# schematics.net
KiCad netlist of a schematic drawn in EAGLE
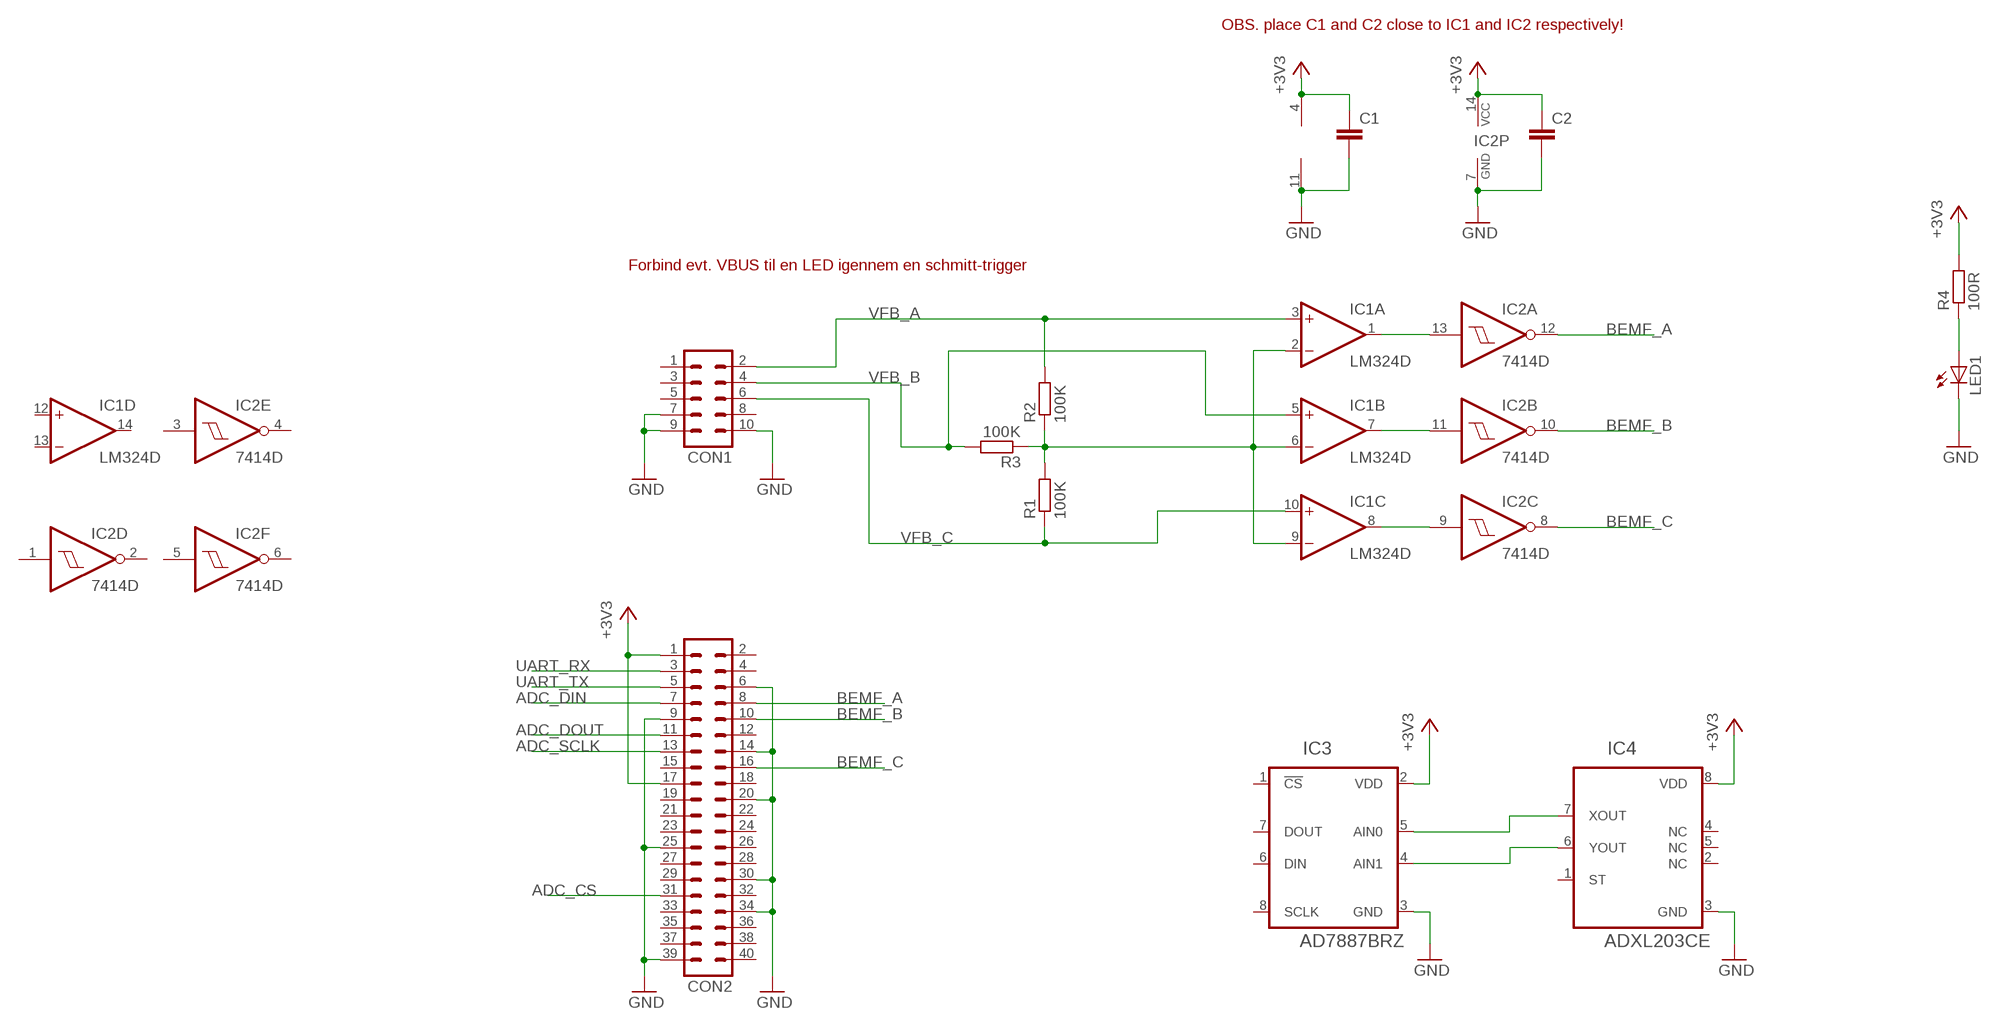
[diagram p0: schematic, sheet 1]

(export (version "E")
  (design (tool "Eeschema 10.0.6"))
  (components
    (comp (ref "C1")
      (value "C-EUC0805K")
      (footprint "eagle-import:C0805K")
      (libsource (lib "eagle-import") (part "C-EUC0805K"))
    )
    (comp (ref "C2")
      (value "C-EUC0805K")
      (footprint "eagle-import:C0805K")
      (libsource (lib "eagle-import") (part "C-EUC0805K"))
    )
    (comp (ref "CON1")
      (value "MA05-2")
      (footprint "eagle-import:MA05-2")
      (libsource (lib "eagle-import") (part "MA05-2"))
    )
    (comp (ref "CON2")
      (value "MA20-2")
      (footprint "eagle-import:MA20-2")
      (libsource (lib "eagle-import") (part "MA20-2"))
    )
    (comp (ref "IC1")
      (value "LM324D")
      (footprint "eagle-import:SO14")
      (libsource (lib "eagle-import") (part "LM324D"))
    )
    (comp (ref "IC2")
      (value "7414D")
      (footprint "eagle-import:SO14")
      (libsource (lib "eagle-import") (part "7414D"))
    )
    (comp (ref "IC3")
      (value "AD7887BRZ")
      (footprint "eagle-import:SO08")
      (libsource (lib "eagle-import") (part "AD7887BRZ"))
    )
    (comp (ref "IC4")
      (value "ADXL203CE")
      (footprint "eagle-import:LCC127P500X500X220-8N")
      (fields (field (name "MF") "Analog Devices") (field (name "MP") "ADXL203CE-REEL"))
      (libsource (lib "eagle-import") (part "ADXL203CE"))
    )
    (comp (ref "LED1")
      (value "LEDCHIP-LED0805")
      (footprint "eagle-import:CHIP-LED0805")
      (libsource (lib "eagle-import") (part "LEDCHIP-LED0805"))
    )
    (comp (ref "R1")
      (value "100K")
      (footprint "eagle-import:R0805")
      (libsource (lib "eagle-import") (part "R-EU_R0805"))
    )
    (comp (ref "R2")
      (value "100K")
      (footprint "eagle-import:R0805")
      (libsource (lib "eagle-import") (part "R-EU_R0805"))
    )
    (comp (ref "R3")
      (value "100K")
      (footprint "eagle-import:R0805")
      (libsource (lib "eagle-import") (part "R-EU_R0805"))
    )
    (comp (ref "R4")
      (value "100R")
      (footprint "eagle-import:R0805")
      (libsource (lib "eagle-import") (part "R-EU_R0805"))
    )
  )
  (nets
    (net (code "1") (name "+3V3") (class "Default")
      (node (ref "C1") (pin "1") (pinfunction "1_1") (pintype "passive"))
      (node (ref "C2") (pin "1") (pinfunction "1_1") (pintype "passive"))
      (node (ref "CON2") (pin "1") (pinfunction "1_1") (pintype "passive"))
      (node (ref "CON2") (pin "17") (pinfunction "17_17") (pintype "passive"))
      (node (ref "IC1") (pin "4") (pinfunction "V+_4") (pintype "power_in"))
      (node (ref "IC2") (pin "14") (pinfunction "VCC_14") (pintype "power_in"))
      (node (ref "IC3") (pin "2") (pinfunction "VDD_2") (pintype "power_in"))
      (node (ref "IC4") (pin "8") (pinfunction "VDD_8") (pintype "power_in"))
      (node (ref "R4") (pin "2") (pinfunction "2_2") (pintype "passive"))
    )
    (net (code "2") (name "/ADC_CS") (class "Default")
      (node (ref "CON2") (pin "31") (pinfunction "31_31") (pintype "passive"))
    )
    (net (code "3") (name "/ADC_DIN") (class "Default")
      (node (ref "CON2") (pin "7") (pinfunction "7_7") (pintype "passive"))
    )
    (net (code "4") (name "/ADC_DOUT") (class "Default")
      (node (ref "CON2") (pin "11") (pinfunction "11_11") (pintype "passive"))
    )
    (net (code "5") (name "/ADC_SCLK") (class "Default")
      (node (ref "CON2") (pin "13") (pinfunction "13_13") (pintype "passive"))
    )
    (net (code "6") (name "/BEMF_A") (class "Default")
      (node (ref "CON2") (pin "8") (pinfunction "8_8") (pintype "passive"))
      (node (ref "IC2") (pin "12") (pinfunction "O_12") (pintype "output"))
    )
    (net (code "7") (name "/BEMF_B") (class "Default")
      (node (ref "CON2") (pin "10") (pinfunction "10_10") (pintype "passive"))
      (node (ref "IC2") (pin "10") (pinfunction "O_10") (pintype "output"))
    )
    (net (code "8") (name "/BEMF_C") (class "Default")
      (node (ref "CON2") (pin "16") (pinfunction "16_16") (pintype "passive"))
      (node (ref "IC2") (pin "8") (pinfunction "O_8") (pintype "output"))
    )
    (net (code "9") (name "/UART_RX") (class "Default")
      (node (ref "CON2") (pin "3") (pinfunction "3_3") (pintype "passive"))
    )
    (net (code "10") (name "/UART_TX") (class "Default")
      (node (ref "CON2") (pin "5") (pinfunction "5_5") (pintype "passive"))
    )
    (net (code "11") (name "/VFB_A") (class "Default")
      (node (ref "CON1") (pin "2") (pinfunction "2_2") (pintype "passive"))
      (node (ref "IC1") (pin "3") (pinfunction "+IN_3") (pintype "input"))
      (node (ref "R2") (pin "2") (pinfunction "2_2") (pintype "passive"))
    )
    (net (code "12") (name "/VFB_B") (class "Default")
      (node (ref "CON1") (pin "4") (pinfunction "4_4") (pintype "passive"))
      (node (ref "IC1") (pin "5") (pinfunction "+IN_5") (pintype "input"))
      (node (ref "R3") (pin "2") (pinfunction "2_2") (pintype "passive"))
    )
    (net (code "13") (name "/VFB_C") (class "Default")
      (node (ref "CON1") (pin "6") (pinfunction "6_6") (pintype "passive"))
      (node (ref "IC1") (pin "10") (pinfunction "+IN_10") (pintype "input"))
      (node (ref "R1") (pin "1") (pinfunction "1_1") (pintype "passive"))
    )
    (net (code "14") (name "GND") (class "Default")
      (node (ref "C1") (pin "2") (pinfunction "2_2") (pintype "passive"))
      (node (ref "C2") (pin "2") (pinfunction "2_2") (pintype "passive"))
      (node (ref "CON1") (pin "10") (pinfunction "10_10") (pintype "passive"))
      (node (ref "CON1") (pin "7") (pinfunction "7_7") (pintype "passive"))
      (node (ref "CON1") (pin "9") (pinfunction "9_9") (pintype "passive"))
      (node (ref "CON2") (pin "14") (pinfunction "14_14") (pintype "passive"))
      (node (ref "CON2") (pin "20") (pinfunction "20_20") (pintype "passive"))
      (node (ref "CON2") (pin "25") (pinfunction "25_25") (pintype "passive"))
      (node (ref "CON2") (pin "30") (pinfunction "30_30") (pintype "passive"))
      (node (ref "CON2") (pin "34") (pinfunction "34_34") (pintype "passive"))
      (node (ref "CON2") (pin "39") (pinfunction "39_39") (pintype "passive"))
      (node (ref "CON2") (pin "6") (pinfunction "6_6") (pintype "passive"))
      (node (ref "CON2") (pin "9") (pinfunction "9_9") (pintype "passive"))
      (node (ref "IC1") (pin "11") (pinfunction "V-_11") (pintype "power_in"))
      (node (ref "IC2") (pin "7") (pinfunction "GND_7") (pintype "power_in"))
      (node (ref "IC3") (pin "3") (pinfunction "GND_3") (pintype "power_in"))
      (node (ref "IC4") (pin "3") (pinfunction "GND_3") (pintype "power_in"))
      (node (ref "LED1") (pin "C") (pinfunction "C_C") (pintype "passive"))
    )
    (net (code "15") (name "Net-(IC1A--IN)") (class "Default")
      (node (ref "IC1") (pin "2") (pinfunction "-IN_2") (pintype "input"))
      (node (ref "IC1") (pin "6") (pinfunction "-IN_6") (pintype "input"))
      (node (ref "IC1") (pin "9") (pinfunction "-IN_9") (pintype "input"))
      (node (ref "R1") (pin "2") (pinfunction "2_2") (pintype "passive"))
      (node (ref "R2") (pin "1") (pinfunction "1_1") (pintype "passive"))
      (node (ref "R3") (pin "1") (pinfunction "1_1") (pintype "passive"))
    )
    (net (code "16") (name "Net-(IC1A-OUT)") (class "Default")
      (node (ref "IC1") (pin "1") (pinfunction "OUT_1") (pintype "output"))
      (node (ref "IC2") (pin "13") (pinfunction "I_13") (pintype "input"))
    )
    (net (code "17") (name "Net-(IC1B-OUT)") (class "Default")
      (node (ref "IC1") (pin "7") (pinfunction "OUT_7") (pintype "output"))
      (node (ref "IC2") (pin "11") (pinfunction "I_11") (pintype "input"))
    )
    (net (code "18") (name "Net-(IC1C-OUT)") (class "Default")
      (node (ref "IC1") (pin "8") (pinfunction "OUT_8") (pintype "output"))
      (node (ref "IC2") (pin "9") (pinfunction "I_9") (pintype "input"))
    )
    (net (code "19") (name "Net-(IC3-AIN0)") (class "Default")
      (node (ref "IC3") (pin "5") (pinfunction "AIN0_5") (pintype "input"))
      (node (ref "IC4") (pin "7") (pinfunction "XOUT_7") (pintype "output"))
    )
    (net (code "20") (name "Net-(IC3-AIN1)") (class "Default")
      (node (ref "IC3") (pin "4") (pinfunction "AIN1_4") (pintype "input"))
      (node (ref "IC4") (pin "6") (pinfunction "YOUT_6") (pintype "output"))
    )
    (net (code "21") (name "Net-(LED1-PadA)") (class "Default")
      (node (ref "LED1") (pin "A") (pinfunction "A_A") (pintype "passive"))
      (node (ref "R4") (pin "1") (pinfunction "1_1") (pintype "passive"))
    )
    (net (code "22") (name "unconnected-(CON1-Pad1)") (class "Default")
      (node (ref "CON1") (pin "1") (pinfunction "1_1") (pintype "passive"))
    )
    (net (code "23") (name "unconnected-(CON1-Pad3)") (class "Default")
      (node (ref "CON1") (pin "3") (pinfunction "3_3") (pintype "passive"))
    )
    (net (code "24") (name "unconnected-(CON1-Pad5)") (class "Default")
      (node (ref "CON1") (pin "5") (pinfunction "5_5") (pintype "passive"))
    )
    (net (code "25") (name "unconnected-(CON1-Pad8)") (class "Default")
      (node (ref "CON1") (pin "8") (pinfunction "8_8") (pintype "passive"))
    )
    (net (code "26") (name "unconnected-(CON2-Pad2)") (class "Default")
      (node (ref "CON2") (pin "2") (pinfunction "2_2") (pintype "passive"))
    )
    (net (code "27") (name "unconnected-(CON2-Pad4)") (class "Default")
      (node (ref "CON2") (pin "4") (pinfunction "4_4") (pintype "passive"))
    )
    (net (code "28") (name "unconnected-(CON2-Pad12)") (class "Default")
      (node (ref "CON2") (pin "12") (pinfunction "12_12") (pintype "passive"))
    )
    (net (code "29") (name "unconnected-(CON2-Pad15)") (class "Default")
      (node (ref "CON2") (pin "15") (pinfunction "15_15") (pintype "passive"))
    )
    (net (code "30") (name "unconnected-(CON2-Pad18)") (class "Default")
      (node (ref "CON2") (pin "18") (pinfunction "18_18") (pintype "passive"))
    )
    (net (code "31") (name "unconnected-(CON2-Pad19)") (class "Default")
      (node (ref "CON2") (pin "19") (pinfunction "19_19") (pintype "passive"))
    )
    (net (code "32") (name "unconnected-(CON2-Pad21)") (class "Default")
      (node (ref "CON2") (pin "21") (pinfunction "21_21") (pintype "passive"))
    )
    (net (code "33") (name "unconnected-(CON2-Pad22)") (class "Default")
      (node (ref "CON2") (pin "22") (pinfunction "22_22") (pintype "passive"))
    )
    (net (code "34") (name "unconnected-(CON2-Pad23)") (class "Default")
      (node (ref "CON2") (pin "23") (pinfunction "23_23") (pintype "passive"))
    )
    (net (code "35") (name "unconnected-(CON2-Pad24)") (class "Default")
      (node (ref "CON2") (pin "24") (pinfunction "24_24") (pintype "passive"))
    )
    (net (code "36") (name "unconnected-(CON2-Pad26)") (class "Default")
      (node (ref "CON2") (pin "26") (pinfunction "26_26") (pintype "passive"))
    )
    (net (code "37") (name "unconnected-(CON2-Pad27)") (class "Default")
      (node (ref "CON2") (pin "27") (pinfunction "27_27") (pintype "passive"))
    )
    (net (code "38") (name "unconnected-(CON2-Pad28)") (class "Default")
      (node (ref "CON2") (pin "28") (pinfunction "28_28") (pintype "passive"))
    )
    (net (code "39") (name "unconnected-(CON2-Pad29)") (class "Default")
      (node (ref "CON2") (pin "29") (pinfunction "29_29") (pintype "passive"))
    )
    (net (code "40") (name "unconnected-(CON2-Pad32)") (class "Default")
      (node (ref "CON2") (pin "32") (pinfunction "32_32") (pintype "passive"))
    )
    (net (code "41") (name "unconnected-(CON2-Pad33)") (class "Default")
      (node (ref "CON2") (pin "33") (pinfunction "33_33") (pintype "passive"))
    )
    (net (code "42") (name "unconnected-(CON2-Pad35)") (class "Default")
      (node (ref "CON2") (pin "35") (pinfunction "35_35") (pintype "passive"))
    )
    (net (code "43") (name "unconnected-(CON2-Pad36)") (class "Default")
      (node (ref "CON2") (pin "36") (pinfunction "36_36") (pintype "passive"))
    )
    (net (code "44") (name "unconnected-(CON2-Pad37)") (class "Default")
      (node (ref "CON2") (pin "37") (pinfunction "37_37") (pintype "passive"))
    )
    (net (code "45") (name "unconnected-(CON2-Pad38)") (class "Default")
      (node (ref "CON2") (pin "38") (pinfunction "38_38") (pintype "passive"))
    )
    (net (code "46") (name "unconnected-(CON2-Pad40)") (class "Default")
      (node (ref "CON2") (pin "40") (pinfunction "40_40") (pintype "passive"))
    )
    (net (code "47") (name "unconnected-(IC1D-+IN-Pad12)") (class "Default")
      (node (ref "IC1") (pin "12") (pinfunction "+IN_12") (pintype "input"))
    )
    (net (code "48") (name "unconnected-(IC1D--IN-Pad13)") (class "Default")
      (node (ref "IC1") (pin "13") (pinfunction "-IN_13") (pintype "input"))
    )
    (net (code "49") (name "unconnected-(IC1D-OUT-Pad14)") (class "Default")
      (node (ref "IC1") (pin "14") (pinfunction "OUT_14") (pintype "output"))
    )
    (net (code "50") (name "unconnected-(IC2D-I-Pad1)") (class "Default")
      (node (ref "IC2") (pin "1") (pinfunction "I_1") (pintype "input"))
    )
    (net (code "51") (name "unconnected-(IC2D-O-Pad2)") (class "Default")
      (node (ref "IC2") (pin "2") (pinfunction "O_2") (pintype "output"))
    )
    (net (code "52") (name "unconnected-(IC2E-I-Pad3)") (class "Default")
      (node (ref "IC2") (pin "3") (pinfunction "I_3") (pintype "input"))
    )
    (net (code "53") (name "unconnected-(IC2E-O-Pad4)") (class "Default")
      (node (ref "IC2") (pin "4") (pinfunction "O_4") (pintype "output"))
    )
    (net (code "54") (name "unconnected-(IC2F-I-Pad5)") (class "Default")
      (node (ref "IC2") (pin "5") (pinfunction "I_5") (pintype "input"))
    )
    (net (code "55") (name "unconnected-(IC2F-O-Pad6)") (class "Default")
      (node (ref "IC2") (pin "6") (pinfunction "O_6") (pintype "output"))
    )
    (net (code "56") (name "unconnected-(IC3-DIN-Pad6)") (class "Default")
      (node (ref "IC3") (pin "6") (pinfunction "DIN_6") (pintype "input"))
    )
    (net (code "57") (name "unconnected-(IC3-DOUT-Pad7)") (class "Default")
      (node (ref "IC3") (pin "7") (pinfunction "DOUT_7") (pintype "output"))
    )
    (net (code "58") (name "unconnected-(IC3-SCLK-Pad8)") (class "Default")
      (node (ref "IC3") (pin "8") (pinfunction "SCLK_8") (pintype "input"))
    )
    (net (code "59") (name "unconnected-(IC3-~{CS}-Pad1)") (class "Default")
      (node (ref "IC3") (pin "1") (pinfunction "~{CS}_1") (pintype "bidirectional"))
    )
    (net (code "60") (name "unconnected-(IC4-NC-Pad2)") (class "Default")
      (node (ref "IC4") (pin "2") (pinfunction "NC_2") (pintype "passive"))
    )
    (net (code "61") (name "unconnected-(IC4-NC-Pad4)") (class "Default")
      (node (ref "IC4") (pin "4") (pinfunction "NC_4") (pintype "passive"))
    )
    (net (code "62") (name "unconnected-(IC4-NC-Pad5)") (class "Default")
      (node (ref "IC4") (pin "5") (pinfunction "NC_5") (pintype "passive"))
    )
    (net (code "63") (name "unconnected-(IC4-ST-Pad1)") (class "Default")
      (node (ref "IC4") (pin "1") (pinfunction "ST_1") (pintype "input"))
    )
  )
)
